# Top.net
KiCad netlist of a schematic drawn in Altium Designer
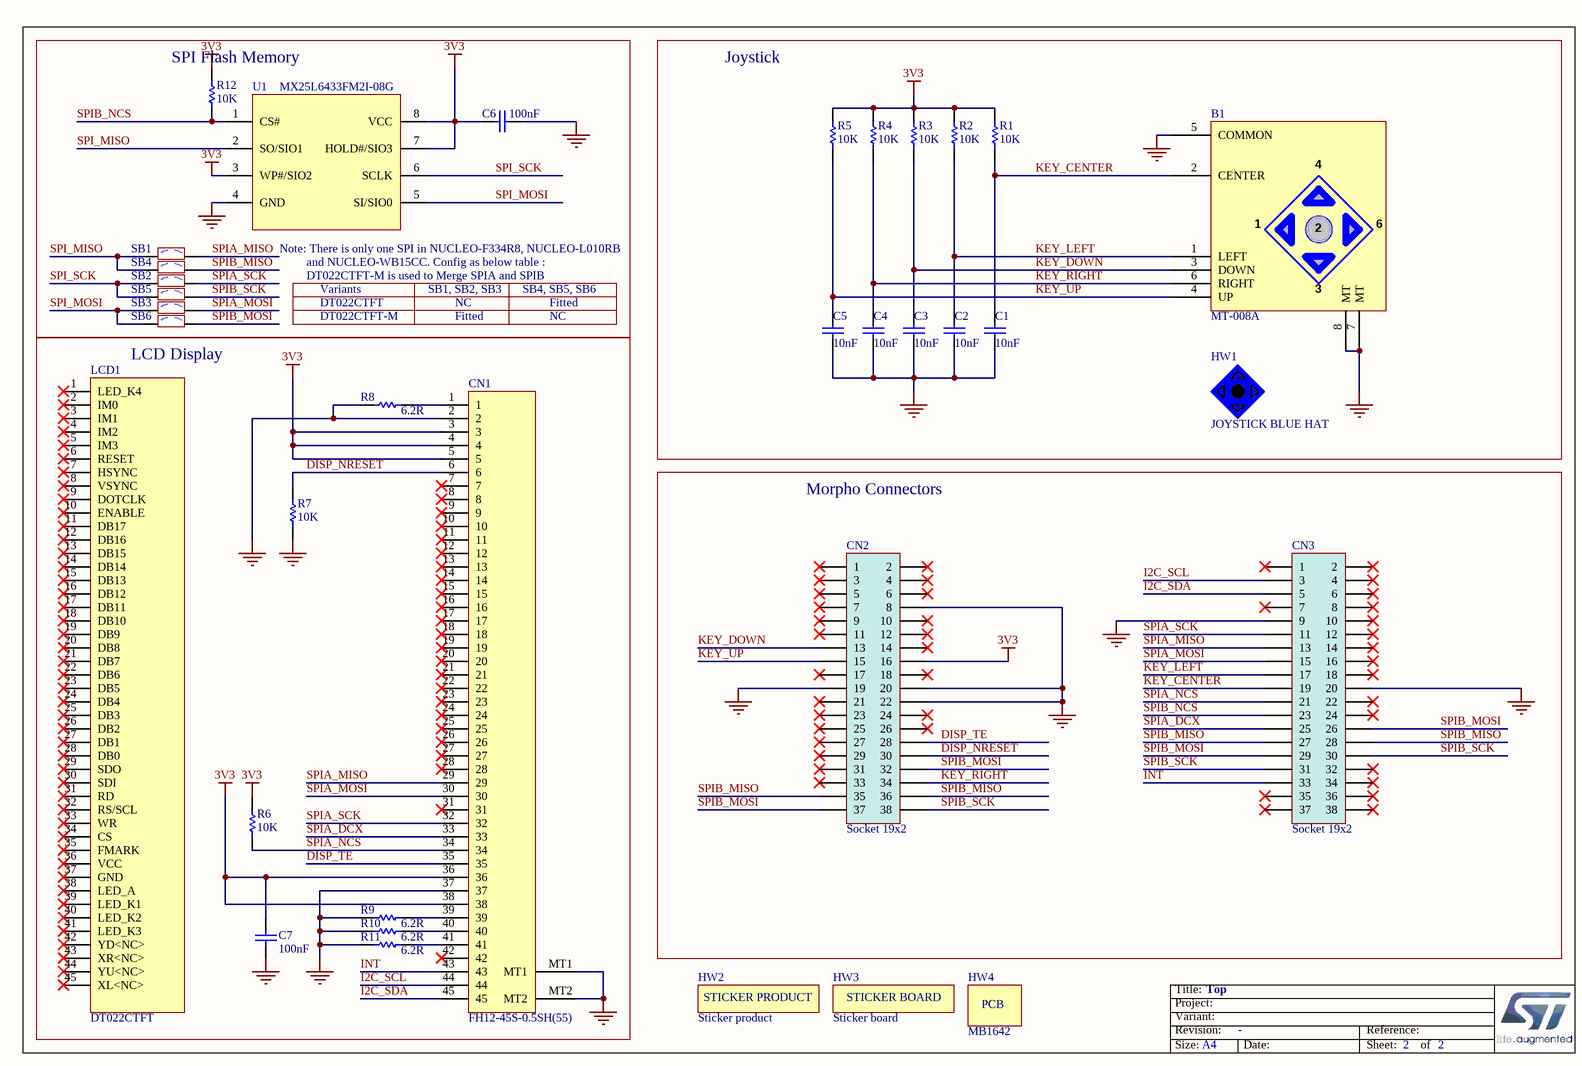
[diagram p0: Top.SchDoc]

(export (version "E")
  (design (tool "Eeschema 10.0.6"))
  (components
    (comp (ref "B1")
      (value "MT-008A")
      (footprint "SWI_XIEJIA_MT-008A_6P")
      (description "Joystick, 4 dir, 1 OK")
      (fields
        (field (name "INTERNAL_PART_NUMBER") "MCD-00132")
        (field (name "MANUFACTURER") "XIEJIA ELECTRONICS")
        (field (name "PROVIDED_BY") "SUBCO")
      )
      (libsource (lib "MCD_PARTS_database") (part "Joystick MT-008A_M"))
    )
    (comp (ref "C1")
      (value "10nF")
      (footprint "C0603")
      (description "Capacitor,10nF,100V,X7R,10%,0603")
      (fields
        (field (name "INTERNAL_PART_NUMBER") "MCD-01098")
        (field (name "MANUFACTURER_PART_NUMBER") "CC0603KRX7R0BB103")
        (field (name "PROVIDED_BY") "SUBCO")
      )
      (libsource (lib "MCD_PARTS_database") (part "Capacitor"))
    )
    (comp (ref "C2")
      (value "10nF")
      (footprint "C0603")
      (description "Capacitor,10nF,100V,X7R,10%,0603")
      (fields
        (field (name "INTERNAL_PART_NUMBER") "MCD-01098")
        (field (name "MANUFACTURER_PART_NUMBER") "CC0603KRX7R0BB103")
        (field (name "PROVIDED_BY") "SUBCO")
      )
      (libsource (lib "MCD_PARTS_database") (part "Capacitor"))
    )
    (comp (ref "C3")
      (value "10nF")
      (footprint "C0603")
      (description "Capacitor,10nF,100V,X7R,10%,0603")
      (fields
        (field (name "INTERNAL_PART_NUMBER") "MCD-01098")
        (field (name "MANUFACTURER_PART_NUMBER") "CC0603KRX7R0BB103")
        (field (name "PROVIDED_BY") "SUBCO")
      )
      (libsource (lib "MCD_PARTS_database") (part "Capacitor"))
    )
    (comp (ref "C4")
      (value "10nF")
      (footprint "C0603")
      (description "Capacitor,10nF,100V,X7R,10%,0603")
      (fields
        (field (name "INTERNAL_PART_NUMBER") "MCD-01098")
        (field (name "MANUFACTURER_PART_NUMBER") "CC0603KRX7R0BB103")
        (field (name "PROVIDED_BY") "SUBCO")
      )
      (libsource (lib "MCD_PARTS_database") (part "Capacitor"))
    )
    (comp (ref "C5")
      (value "10nF")
      (footprint "C0603")
      (description "Capacitor,10nF,100V,X7R,10%,0603")
      (fields
        (field (name "INTERNAL_PART_NUMBER") "MCD-01098")
        (field (name "MANUFACTURER_PART_NUMBER") "CC0603KRX7R0BB103")
        (field (name "PROVIDED_BY") "SUBCO")
      )
      (libsource (lib "MCD_PARTS_database") (part "Capacitor"))
    )
    (comp (ref "C6")
      (value "100nF")
      (footprint "C0603")
      (description "Capacitor, MLCC, 100nF, 16V, X7R, +/-10%, 0603, T=0,8mm")
      (fields (field (name "INTERNAL_PART_NUMBER") "MCD-00211") (field (name "MANUFACTURER") "YAGEO"))
      (libsource (lib "MCD_PARTS_database") (part "Capacitor"))
    )
    (comp (ref "C7")
      (value "100nF")
      (footprint "C0603")
      (description "Capacitor, MLCC, 100nF, 16V, X7R, +/-10%, 0603, T=0,8mm")
      (fields (field (name "INTERNAL_PART_NUMBER") "MCD-00211") (field (name "MANUFACTURER") "YAGEO"))
      (libsource (lib "MCD_PARTS_database") (part "Capacitor"))
    )
    (comp (ref "CN1")
      (value "FH12-45S-0.5SH(55)")
      (footprint "CON_HRS_FH12-45S-05SH")
      (description "45 pins P 0.5 surface mount connector")
      (fields
        (field (name "INTERNAL_PART_NUMBER") "MCD-01980")
        (field (name "MANUFACTURER") "HIROSE")
        (field (name "PROVIDED_BY") "SUBCO")
      )
      (libsource (lib "MCD_PARTS_database") (part "FH12-45S-0.5SH(55)"))
    )
    (comp (ref "CN2")
      (value "Socket 19x2")
      (footprint "CON_SAMTEC_SSW-119-01-X-D")
      (description "Socket, 19x2, 2.54mm, VR, TH, Height 8.51mm/2.64mm")
      (fields
        (field (name "INTERNAL_PART_NUMBER") "MCD-01845")
        (field (name "MANUFACTURER_PART_NUMBER") "SSW-119-01-x-D")
        (field (name "PROVIDED_BY") "SUBCO")
      )
      (libsource (lib "MCD_PARTS_database") (part "Socket 19x2"))
    )
    (comp (ref "CN3")
      (value "Socket 19x2")
      (footprint "CON_SAMTEC_SSW-119-01-X-D")
      (description "Socket, 19x2, 2.54mm, VR, TH, Height 8.51mm/2.64mm")
      (fields
        (field (name "INTERNAL_PART_NUMBER") "MCD-01845")
        (field (name "MANUFACTURER_PART_NUMBER") "SSW-119-01-x-D")
        (field (name "PROVIDED_BY") "SUBCO")
      )
      (libsource (lib "MCD_PARTS_database") (part "Socket 19x2"))
    )
    (comp (ref "HW1")
      (value "JOYSTICK BLUE HAT")
      (description "Joystick Blue Hat")
      (fields
        (field (name "INTERNAL_PART_NUMBER") "MCD-01337")
        (field (name "MANUFACTURER_PART_NUMBER") "PB-504")
        (field (name "PROVIDED_BY") "SUBCO")
      )
      (libsource (lib "MCD_PARTS_database") (part "JOYSTICK_BLUE_HAT"))
    )
    (comp (ref "HW2")
      (value "Sticker product")
      (footprint "STICKER_PRODUCT_25X5")
      (description "Sticker product 25x5 mm")
      (fields (field (name "INTERNAL_PART_NUMBER") "MCD-02189") (field (name "Comment") "STICKER_PRODUCT"))
      (libsource (lib "MCD_PARTS_database") (part "STICKER_PRODUCT"))
    )
    (comp (ref "HW3")
      (value "Sticker board")
      (footprint "STICKER_BOARD_25X5")
      (description "Sticker board 25x5 mm")
      (fields (field (name "INTERNAL_PART_NUMBER") "MCD-02190") (field (name "Comment") "STICKER_BOARD"))
      (libsource (lib "MCD_PARTS_database") (part "STICKER_BOARD"))
    )
    (comp (ref "HW4")
      (value "MB1642")
      (description "MB1642 PCB")
      (fields (field (name "INTERNAL_PART_NUMBER") "MCD-02495") (field (name "Comment") "PCB"))
      (libsource (lib "MCD_PARTS_database") (part "PCB"))
    )
    (comp (ref "LCD1")
      (value "DT022CTFT")
      (footprint "LCD_DISPLAYTECH_DT022CTFT_45P_P050")
      (description "240x320 2.2inch display")
      (fields
        (field (name "INTERNAL_PART_NUMBER") "MCD-01982")
        (field (name "MANUFACTURER") "DISPLAYTECH")
        (field (name "PROVIDED_BY") "SUBCO")
      )
      (libsource (lib "MCD_PARTS_database") (part "DT022CTFT"))
    )
    (comp (ref "R1")
      (value "10K")
      (footprint "R0603")
      (description "Resistor,10K,0603,1%,1/10W")
      (fields
        (field (name "INTERNAL_PART_NUMBER") "MCD-00220")
        (field (name "MANUFACTURER_PART_NUMBER") "RC0603FR-0710KL")
        (field (name "PROVIDED_BY") "SUBCO")
      )
      (libsource (lib "MCD_PARTS_database") (part "Resistor"))
    )
    (comp (ref "R2")
      (value "10K")
      (footprint "R0603")
      (description "Resistor,10K,0603,1%,1/10W")
      (fields
        (field (name "INTERNAL_PART_NUMBER") "MCD-00220")
        (field (name "MANUFACTURER_PART_NUMBER") "RC0603FR-0710KL")
        (field (name "PROVIDED_BY") "SUBCO")
      )
      (libsource (lib "MCD_PARTS_database") (part "Resistor"))
    )
    (comp (ref "R3")
      (value "10K")
      (footprint "R0603")
      (description "Resistor,10K,0603,1%,1/10W")
      (fields
        (field (name "INTERNAL_PART_NUMBER") "MCD-00220")
        (field (name "MANUFACTURER_PART_NUMBER") "RC0603FR-0710KL")
        (field (name "PROVIDED_BY") "SUBCO")
      )
      (libsource (lib "MCD_PARTS_database") (part "Resistor"))
    )
    (comp (ref "R4")
      (value "10K")
      (footprint "R0603")
      (description "Resistor,10K,0603,1%,1/10W")
      (fields
        (field (name "INTERNAL_PART_NUMBER") "MCD-00220")
        (field (name "MANUFACTURER_PART_NUMBER") "RC0603FR-0710KL")
        (field (name "PROVIDED_BY") "SUBCO")
      )
      (libsource (lib "MCD_PARTS_database") (part "Resistor"))
    )
    (comp (ref "R5")
      (value "10K")
      (footprint "R0603")
      (description "Resistor,10K,0603,1%,1/10W")
      (fields
        (field (name "INTERNAL_PART_NUMBER") "MCD-00220")
        (field (name "MANUFACTURER_PART_NUMBER") "RC0603FR-0710KL")
        (field (name "PROVIDED_BY") "SUBCO")
      )
      (libsource (lib "MCD_PARTS_database") (part "Resistor"))
    )
    (comp (ref "R6")
      (value "10K")
      (footprint "R0603")
      (description "Resistor,10K,0603,1%,1/10W")
      (fields
        (field (name "INTERNAL_PART_NUMBER") "MCD-00220")
        (field (name "MANUFACTURER_PART_NUMBER") "RC0603FR-0710KL")
        (field (name "PROVIDED_BY") "SUBCO")
      )
      (libsource (lib "MCD_PARTS_database") (part "Resistor"))
    )
    (comp (ref "R7")
      (value "10K")
      (footprint "R0603")
      (description "Resistor,10K,0603,1%,1/10W")
      (fields
        (field (name "INTERNAL_PART_NUMBER") "MCD-00220")
        (field (name "MANUFACTURER_PART_NUMBER") "RC0603FR-0710KL")
        (field (name "PROVIDED_BY") "SUBCO")
      )
      (libsource (lib "MCD_PARTS_database") (part "Resistor"))
    )
    (comp (ref "R8")
      (value "6.2R")
      (footprint "R1206_H0P55")
      (description "Resistor,6.2R,1206,1%,0.5W")
      (fields
        (field (name "INTERNAL_PART_NUMBER") "MCD-02101")
        (field (name "MANUFACTURER_PART_NUMBER") "ERJ8BQF6R2V")
        (field (name "PROVIDED_BY") "SUBCO")
      )
      (libsource (lib "MCD_PARTS_database") (part "Resistor"))
    )
    (comp (ref "R9")
      (value "6.2R")
      (footprint "R1206_H0P55")
      (description "Resistor,6.2R,1206,1%,0.5W")
      (fields
        (field (name "INTERNAL_PART_NUMBER") "MCD-02101")
        (field (name "MANUFACTURER_PART_NUMBER") "ERJ8BQF6R2V")
        (field (name "PROVIDED_BY") "SUBCO")
      )
      (libsource (lib "MCD_PARTS_database") (part "Resistor"))
    )
    (comp (ref "R10")
      (value "6.2R")
      (footprint "R1206_H0P55")
      (description "Resistor,6.2R,1206,1%,0.5W")
      (fields
        (field (name "INTERNAL_PART_NUMBER") "MCD-02101")
        (field (name "MANUFACTURER_PART_NUMBER") "ERJ8BQF6R2V")
        (field (name "PROVIDED_BY") "SUBCO")
      )
      (libsource (lib "MCD_PARTS_database") (part "Resistor"))
    )
    (comp (ref "R11")
      (value "6.2R")
      (footprint "R1206_H0P55")
      (description "Resistor,6.2R,1206,1%,0.5W")
      (fields
        (field (name "INTERNAL_PART_NUMBER") "MCD-02101")
        (field (name "MANUFACTURER_PART_NUMBER") "ERJ8BQF6R2V")
        (field (name "PROVIDED_BY") "SUBCO")
      )
      (libsource (lib "MCD_PARTS_database") (part "Resistor"))
    )
    (comp (ref "R12")
      (value "10K")
      (footprint "R0603")
      (description "Resistor,10K,0603,1%,1/10W")
      (fields
        (field (name "INTERNAL_PART_NUMBER") "MCD-00220")
        (field (name "MANUFACTURER_PART_NUMBER") "RC0603FR-0710KL")
        (field (name "PROVIDED_BY") "SUBCO")
      )
      (libsource (lib "MCD_PARTS_database") (part "Resistor"))
    )
    (comp (ref "SB1")
      (value "SB_OFF")
      (footprint "SOLDER-BRIDGE_R0603-0R")
      (description "Solder Bridge OFF")
      (fields (field (name "INTERNAL_PART_NUMBER") "MCD-00072") (field (name "MANUFACTURER") "YAGEO"))
      (libsource (lib "MCD_PARTS_database") (part "SB_OFF"))
    )
    (comp (ref "SB2")
      (value "SB_OFF")
      (footprint "SOLDER-BRIDGE_R0603-0R")
      (description "Solder Bridge OFF")
      (fields (field (name "INTERNAL_PART_NUMBER") "MCD-00072") (field (name "MANUFACTURER") "YAGEO"))
      (libsource (lib "MCD_PARTS_database") (part "SB_OFF"))
    )
    (comp (ref "SB3")
      (value "SB_OFF")
      (footprint "SOLDER-BRIDGE_R0603-0R")
      (description "Solder Bridge OFF")
      (fields (field (name "INTERNAL_PART_NUMBER") "MCD-00072") (field (name "MANUFACTURER") "YAGEO"))
      (libsource (lib "MCD_PARTS_database") (part "SB_OFF"))
    )
    (comp (ref "SB4")
      (value "SB_OFF")
      (footprint "SOLDER-BRIDGE_R0603-0R")
      (description "Solder Bridge OFF")
      (fields (field (name "INTERNAL_PART_NUMBER") "MCD-00072") (field (name "MANUFACTURER") "YAGEO"))
      (libsource (lib "MCD_PARTS_database") (part "SB_OFF"))
    )
    (comp (ref "SB5")
      (value "SB_OFF")
      (footprint "SOLDER-BRIDGE_R0603-0R")
      (description "Solder Bridge OFF")
      (fields (field (name "INTERNAL_PART_NUMBER") "MCD-00072") (field (name "MANUFACTURER") "YAGEO"))
      (libsource (lib "MCD_PARTS_database") (part "SB_OFF"))
    )
    (comp (ref "SB6")
      (value "SB_OFF")
      (footprint "SOLDER-BRIDGE_R0603-0R")
      (description "Solder Bridge OFF")
      (fields (field (name "INTERNAL_PART_NUMBER") "MCD-00072") (field (name "MANUFACTURER") "YAGEO"))
      (libsource (lib "MCD_PARTS_database") (part "SB_OFF"))
    )
    (comp (ref "U1")
      (value "MX25L6433FM2I-08G")
      (footprint "ICC_SOP8_5P23X5P28_P127")
      (fields
        (field (name "INTERNAL_PART_NUMBER") "MCD-01981")
        (field (name "MANUFACTURER") "MACRONIX")
        (field (name "PROVIDED_BY") "SUBCO")
      )
      (libsource (lib "MCD_PARTS_database") (part "MX25L6433FM2I-08G"))
    )
  )
  (nets
    (net (code "1") (name "/DISP_NRESET") (class "Default")
      (node (ref "CN1") (pin "6") (pinfunction "6_6") (pintype "passive"))
      (node (ref "CN2") (pin "30") (pinfunction "30_30") (pintype "passive"))
      (node (ref "R7") (pin "2") (pinfunction "2_2") (pintype "passive"))
    )
    (net (code "2") (name "/DISP_TE") (class "Default")
      (node (ref "CN1") (pin "35") (pinfunction "35_35") (pintype "passive"))
      (node (ref "CN2") (pin "28") (pinfunction "28_28") (pintype "passive"))
    )
    (net (code "3") (name "/I2C_SCL") (class "Default")
      (node (ref "CN1") (pin "44") (pinfunction "44_44") (pintype "passive"))
      (node (ref "CN3") (pin "3") (pinfunction "3_3") (pintype "passive"))
    )
    (net (code "4") (name "/I2C_SDA") (class "Default")
      (node (ref "CN1") (pin "45") (pinfunction "45_45") (pintype "passive"))
      (node (ref "CN3") (pin "5") (pinfunction "5_5") (pintype "passive"))
    )
    (net (code "5") (name "/INT") (class "Default")
      (node (ref "CN1") (pin "43") (pinfunction "43_43") (pintype "passive"))
      (node (ref "CN3") (pin "33") (pinfunction "33_33") (pintype "passive"))
    )
    (net (code "6") (name "/KEY_CENTER") (class "Default")
      (node (ref "B1") (pin "2") (pinfunction "CENTER_2") (pintype "passive"))
      (node (ref "C1") (pin "2") (pinfunction "2_2") (pintype "passive"))
      (node (ref "CN3") (pin "19") (pinfunction "19_19") (pintype "passive"))
      (node (ref "R1") (pin "2") (pinfunction "2_2") (pintype "passive"))
    )
    (net (code "7") (name "/KEY_DOWN") (class "Default")
      (node (ref "B1") (pin "3") (pinfunction "DOWN_3") (pintype "passive"))
      (node (ref "C3") (pin "2") (pinfunction "2_2") (pintype "passive"))
      (node (ref "CN2") (pin "13") (pinfunction "13_13") (pintype "passive"))
      (node (ref "R3") (pin "1") (pinfunction "1_1") (pintype "passive"))
    )
    (net (code "8") (name "/KEY_LEFT") (class "Default")
      (node (ref "B1") (pin "1") (pinfunction "LEFT_1") (pintype "passive"))
      (node (ref "C2") (pin "2") (pinfunction "2_2") (pintype "passive"))
      (node (ref "CN3") (pin "17") (pinfunction "17_17") (pintype "passive"))
      (node (ref "R2") (pin "1") (pinfunction "1_1") (pintype "passive"))
    )
    (net (code "9") (name "/KEY_RIGHT") (class "Default")
      (node (ref "B1") (pin "6") (pinfunction "RIGHT_6") (pintype "passive"))
      (node (ref "C4") (pin "2") (pinfunction "2_2") (pintype "passive"))
      (node (ref "CN2") (pin "34") (pinfunction "34_34") (pintype "passive"))
      (node (ref "R4") (pin "1") (pinfunction "1_1") (pintype "passive"))
    )
    (net (code "10") (name "/KEY_UP") (class "Default")
      (node (ref "B1") (pin "4") (pinfunction "UP_4") (pintype "passive"))
      (node (ref "C5") (pin "2") (pinfunction "2_2") (pintype "passive"))
      (node (ref "CN2") (pin "15") (pinfunction "15_15") (pintype "passive"))
      (node (ref "R5") (pin "1") (pinfunction "1_1") (pintype "passive"))
    )
    (net (code "11") (name "/SPIA_DCX") (class "Default")
      (node (ref "CN1") (pin "33") (pinfunction "33_33") (pintype "passive"))
      (node (ref "CN3") (pin "25") (pinfunction "25_25") (pintype "passive"))
    )
    (net (code "12") (name "/SPIA_MISO") (class "Default")
      (node (ref "CN1") (pin "29") (pinfunction "29_29") (pintype "passive"))
      (node (ref "CN3") (pin "13") (pinfunction "13_13") (pintype "passive"))
      (node (ref "SB1") (pin "2") (pinfunction "2_2") (pintype "passive"))
    )
    (net (code "13") (name "/SPIA_MOSI") (class "Default")
      (node (ref "CN1") (pin "30") (pinfunction "30_30") (pintype "passive"))
      (node (ref "CN3") (pin "15") (pinfunction "15_15") (pintype "passive"))
      (node (ref "SB3") (pin "2") (pinfunction "2_2") (pintype "passive"))
    )
    (net (code "14") (name "/SPIA_NCS") (class "Default")
      (node (ref "CN1") (pin "34") (pinfunction "34_34") (pintype "passive"))
      (node (ref "CN3") (pin "21") (pinfunction "21_21") (pintype "passive"))
      (node (ref "R6") (pin "1") (pinfunction "1_1") (pintype "passive"))
    )
    (net (code "15") (name "/SPIA_SCK") (class "Default")
      (node (ref "CN1") (pin "32") (pinfunction "32_32") (pintype "passive"))
      (node (ref "CN3") (pin "11") (pinfunction "11_11") (pintype "passive"))
      (node (ref "SB2") (pin "2") (pinfunction "2_2") (pintype "passive"))
    )
    (net (code "16") (name "/SPIB_MISO") (class "Default")
      (node (ref "CN2") (pin "35") (pinfunction "35_35") (pintype "passive"))
      (node (ref "CN2") (pin "36") (pinfunction "36_36") (pintype "passive"))
      (node (ref "CN3") (pin "27") (pinfunction "27_27") (pintype "passive"))
      (node (ref "CN3") (pin "28") (pinfunction "28_28") (pintype "passive"))
      (node (ref "SB4") (pin "2") (pinfunction "2_2") (pintype "passive"))
    )
    (net (code "17") (name "/SPIB_MOSI") (class "Default")
      (node (ref "CN2") (pin "32") (pinfunction "32_32") (pintype "passive"))
      (node (ref "CN2") (pin "37") (pinfunction "37_37") (pintype "passive"))
      (node (ref "CN3") (pin "26") (pinfunction "26_26") (pintype "passive"))
      (node (ref "CN3") (pin "29") (pinfunction "29_29") (pintype "passive"))
      (node (ref "SB6") (pin "2") (pinfunction "2_2") (pintype "passive"))
    )
    (net (code "18") (name "/SPIB_NCS") (class "Default")
      (node (ref "CN3") (pin "23") (pinfunction "23_23") (pintype "passive"))
      (node (ref "R12") (pin "2") (pinfunction "2_2") (pintype "passive"))
      (node (ref "U1") (pin "1") (pinfunction "CS#_1") (pintype "passive"))
    )
    (net (code "19") (name "/SPIB_SCK") (class "Default")
      (node (ref "CN2") (pin "38") (pinfunction "38_38") (pintype "passive"))
      (node (ref "CN3") (pin "30") (pinfunction "30_30") (pintype "passive"))
      (node (ref "CN3") (pin "31") (pinfunction "31_31") (pintype "passive"))
      (node (ref "SB5") (pin "2") (pinfunction "2_2") (pintype "passive"))
    )
    (net (code "20") (name "/SPI_MISO") (class "Default")
      (node (ref "SB1") (pin "1") (pinfunction "1_1") (pintype "passive"))
      (node (ref "SB4") (pin "1") (pinfunction "1_1") (pintype "passive"))
      (node (ref "U1") (pin "2") (pinfunction "SO/SIO1_2") (pintype "passive"))
    )
    (net (code "21") (name "/SPI_MOSI") (class "Default")
      (node (ref "SB3") (pin "1") (pinfunction "1_1") (pintype "passive"))
      (node (ref "SB6") (pin "1") (pinfunction "1_1") (pintype "passive"))
      (node (ref "U1") (pin "5") (pinfunction "SI/SIO0_5") (pintype "passive"))
    )
    (net (code "22") (name "/SPI_SCK") (class "Default")
      (node (ref "SB2") (pin "1") (pinfunction "1_1") (pintype "passive"))
      (node (ref "SB5") (pin "1") (pinfunction "1_1") (pintype "passive"))
      (node (ref "U1") (pin "6") (pinfunction "SCLK_6") (pintype "passive"))
    )
    (net (code "23") (name "3V3") (class "Default")
      (node (ref "C6") (pin "1") (pinfunction "1_1") (pintype "passive"))
      (node (ref "C7") (pin "2") (pinfunction "2_2") (pintype "passive"))
      (node (ref "CN1") (pin "3") (pinfunction "3_3") (pintype "passive"))
      (node (ref "CN1") (pin "36") (pinfunction "36_36") (pintype "passive"))
      (node (ref "CN1") (pin "38") (pinfunction "38_38") (pintype "passive"))
      (node (ref "CN1") (pin "4") (pinfunction "4_4") (pintype "passive"))
      (node (ref "CN1") (pin "5") (pinfunction "5_5") (pintype "passive"))
      (node (ref "CN2") (pin "16") (pinfunction "16_16") (pintype "passive"))
      (node (ref "R1") (pin "1") (pinfunction "1_1") (pintype "passive"))
      (node (ref "R12") (pin "1") (pinfunction "1_1") (pintype "passive"))
      (node (ref "R2") (pin "2") (pinfunction "2_2") (pintype "passive"))
      (node (ref "R3") (pin "2") (pinfunction "2_2") (pintype "passive"))
      (node (ref "R4") (pin "2") (pinfunction "2_2") (pintype "passive"))
      (node (ref "R5") (pin "2") (pinfunction "2_2") (pintype "passive"))
      (node (ref "R6") (pin "2") (pinfunction "2_2") (pintype "passive"))
      (node (ref "U1") (pin "3") (pinfunction "WP#/SIO2_3") (pintype "passive"))
      (node (ref "U1") (pin "7") (pinfunction "HOLD#/SIO3_7") (pintype "passive"))
      (node (ref "U1") (pin "8") (pinfunction "VCC_8") (pintype "passive"))
    )
    (net (code "24") (name "GND") (class "Default")
      (node (ref "B1") (pin "5") (pinfunction "COMMON_5") (pintype "passive"))
      (node (ref "B1") (pin "7") (pinfunction "MT_7") (pintype "passive"))
      (node (ref "B1") (pin "8") (pinfunction "MT_8") (pintype "passive"))
      (node (ref "C1") (pin "1") (pinfunction "1_1") (pintype "passive"))
      (node (ref "C2") (pin "1") (pinfunction "1_1") (pintype "passive"))
      (node (ref "C3") (pin "1") (pinfunction "1_1") (pintype "passive"))
      (node (ref "C4") (pin "1") (pinfunction "1_1") (pintype "passive"))
      (node (ref "C5") (pin "1") (pinfunction "1_1") (pintype "passive"))
      (node (ref "C6") (pin "2") (pinfunction "2_2") (pintype "passive"))
      (node (ref "C7") (pin "1") (pinfunction "1_1") (pintype "passive"))
      (node (ref "CN1") (pin "2") (pinfunction "2_2") (pintype "passive"))
      (node (ref "CN1") (pin "37") (pinfunction "37_37") (pintype "passive"))
      (node (ref "CN1") (pin "MT1") (pinfunction "MT1_MT1") (pintype "passive"))
      (node (ref "CN1") (pin "MT2") (pinfunction "MT2_MT2") (pintype "passive"))
      (node (ref "CN2") (pin "19") (pinfunction "19_19") (pintype "passive"))
      (node (ref "CN2") (pin "20") (pinfunction "20_20") (pintype "passive"))
      (node (ref "CN2") (pin "22") (pinfunction "22_22") (pintype "passive"))
      (node (ref "CN2") (pin "8") (pinfunction "8_8") (pintype "passive"))
      (node (ref "CN3") (pin "20") (pinfunction "20_20") (pintype "passive"))
      (node (ref "CN3") (pin "9") (pinfunction "9_9") (pintype "passive"))
      (node (ref "R10") (pin "1") (pinfunction "1_1") (pintype "passive"))
      (node (ref "R11") (pin "1") (pinfunction "1_1") (pintype "passive"))
      (node (ref "R7") (pin "1") (pinfunction "1_1") (pintype "passive"))
      (node (ref "R8") (pin "1") (pinfunction "1_1") (pintype "passive"))
      (node (ref "R9") (pin "1") (pinfunction "1_1") (pintype "passive"))
      (node (ref "U1") (pin "4") (pinfunction "GND_4") (pintype "passive"))
    )
    (net (code "25") (name "Net-(CN1-Pad1)") (class "Default")
      (node (ref "CN1") (pin "1") (pinfunction "1_1") (pintype "passive"))
      (node (ref "R8") (pin "2") (pinfunction "2_2") (pintype "passive"))
    )
    (net (code "26") (name "Net-(CN1-Pad39)") (class "Default")
      (node (ref "CN1") (pin "39") (pinfunction "39_39") (pintype "passive"))
      (node (ref "R9") (pin "2") (pinfunction "2_2") (pintype "passive"))
    )
    (net (code "27") (name "Net-(CN1-Pad40)") (class "Default")
      (node (ref "CN1") (pin "40") (pinfunction "40_40") (pintype "passive"))
      (node (ref "R10") (pin "2") (pinfunction "2_2") (pintype "passive"))
    )
    (net (code "28") (name "Net-(CN1-Pad41)") (class "Default")
      (node (ref "CN1") (pin "41") (pinfunction "41_41") (pintype "passive"))
      (node (ref "R11") (pin "2") (pinfunction "2_2") (pintype "passive"))
    )
    (net (code "29") (name "unconnected-(CN1-Pad7)") (class "Default")
      (node (ref "CN1") (pin "7") (pinfunction "7_7") (pintype "passive+no_connect"))
    )
    (net (code "30") (name "unconnected-(CN1-Pad8)") (class "Default")
      (node (ref "CN1") (pin "8") (pinfunction "8_8") (pintype "passive+no_connect"))
    )
    (net (code "31") (name "unconnected-(CN1-Pad9)") (class "Default")
      (node (ref "CN1") (pin "9") (pinfunction "9_9") (pintype "passive+no_connect"))
    )
    (net (code "32") (name "unconnected-(CN1-Pad10)") (class "Default")
      (node (ref "CN1") (pin "10") (pinfunction "10_10") (pintype "passive+no_connect"))
    )
    (net (code "33") (name "unconnected-(CN1-Pad11)") (class "Default")
      (node (ref "CN1") (pin "11") (pinfunction "11_11") (pintype "passive+no_connect"))
    )
    (net (code "34") (name "unconnected-(CN1-Pad12)") (class "Default")
      (node (ref "CN1") (pin "12") (pinfunction "12_12") (pintype "passive+no_connect"))
    )
    (net (code "35") (name "unconnected-(CN1-Pad13)") (class "Default")
      (node (ref "CN1") (pin "13") (pinfunction "13_13") (pintype "passive+no_connect"))
    )
    (net (code "36") (name "unconnected-(CN1-Pad14)") (class "Default")
      (node (ref "CN1") (pin "14") (pinfunction "14_14") (pintype "passive+no_connect"))
    )
    (net (code "37") (name "unconnected-(CN1-Pad15)") (class "Default")
      (node (ref "CN1") (pin "15") (pinfunction "15_15") (pintype "passive+no_connect"))
    )
    (net (code "38") (name "unconnected-(CN1-Pad16)") (class "Default")
      (node (ref "CN1") (pin "16") (pinfunction "16_16") (pintype "passive+no_connect"))
    )
    (net (code "39") (name "unconnected-(CN1-Pad17)") (class "Default")
      (node (ref "CN1") (pin "17") (pinfunction "17_17") (pintype "passive+no_connect"))
    )
    (net (code "40") (name "unconnected-(CN1-Pad18)") (class "Default")
      (node (ref "CN1") (pin "18") (pinfunction "18_18") (pintype "passive+no_connect"))
    )
    (net (code "41") (name "unconnected-(CN1-Pad19)") (class "Default")
      (node (ref "CN1") (pin "19") (pinfunction "19_19") (pintype "passive+no_connect"))
    )
    (net (code "42") (name "unconnected-(CN1-Pad20)") (class "Default")
      (node (ref "CN1") (pin "20") (pinfunction "20_20") (pintype "passive+no_connect"))
    )
    (net (code "43") (name "unconnected-(CN1-Pad21)") (class "Default")
      (node (ref "CN1") (pin "21") (pinfunction "21_21") (pintype "passive+no_connect"))
    )
    (net (code "44") (name "unconnected-(CN1-Pad22)") (class "Default")
      (node (ref "CN1") (pin "22") (pinfunction "22_22") (pintype "passive+no_connect"))
    )
    (net (code "45") (name "unconnected-(CN1-Pad23)") (class "Default")
      (node (ref "CN1") (pin "23") (pinfunction "23_23") (pintype "passive+no_connect"))
    )
    (net (code "46") (name "unconnected-(CN1-Pad24)") (class "Default")
      (node (ref "CN1") (pin "24") (pinfunction "24_24") (pintype "passive+no_connect"))
    )
    (net (code "47") (name "unconnected-(CN1-Pad25)") (class "Default")
      (node (ref "CN1") (pin "25") (pinfunction "25_25") (pintype "passive+no_connect"))
    )
    (net (code "48") (name "unconnected-(CN1-Pad26)") (class "Default")
      (node (ref "CN1") (pin "26") (pinfunction "26_26") (pintype "passive+no_connect"))
    )
    (net (code "49") (name "unconnected-(CN1-Pad27)") (class "Default")
      (node (ref "CN1") (pin "27") (pinfunction "27_27") (pintype "passive+no_connect"))
    )
    (net (code "50") (name "unconnected-(CN1-Pad28)") (class "Default")
      (node (ref "CN1") (pin "28") (pinfunction "28_28") (pintype "passive+no_connect"))
    )
    (net (code "51") (name "unconnected-(CN1-Pad31)") (class "Default")
      (node (ref "CN1") (pin "31") (pinfunction "31_31") (pintype "passive+no_connect"))
    )
    (net (code "52") (name "unconnected-(CN1-Pad42)") (class "Default")
      (node (ref "CN1") (pin "42") (pinfunction "42_42") (pintype "passive+no_connect"))
    )
    (net (code "53") (name "unconnected-(CN2-Pad1)") (class "Default")
      (node (ref "CN2") (pin "1") (pinfunction "1_1") (pintype "passive+no_connect"))
    )
    (net (code "54") (name "unconnected-(CN2-Pad2)") (class "Default")
      (node (ref "CN2") (pin "2") (pinfunction "2_2") (pintype "passive+no_connect"))
    )
    (net (code "55") (name "unconnected-(CN2-Pad3)") (class "Default")
      (node (ref "CN2") (pin "3") (pinfunction "3_3") (pintype "passive+no_connect"))
    )
    (net (code "56") (name "unconnected-(CN2-Pad4)") (class "Default")
      (node (ref "CN2") (pin "4") (pinfunction "4_4") (pintype "passive+no_connect"))
    )
    (net (code "57") (name "unconnected-(CN2-Pad5)") (class "Default")
      (node (ref "CN2") (pin "5") (pinfunction "5_5") (pintype "passive+no_connect"))
    )
    (net (code "58") (name "unconnected-(CN2-Pad6)") (class "Default")
      (node (ref "CN2") (pin "6") (pinfunction "6_6") (pintype "passive+no_connect"))
    )
    (net (code "59") (name "unconnected-(CN2-Pad7)") (class "Default")
      (node (ref "CN2") (pin "7") (pinfunction "7_7") (pintype "passive+no_connect"))
    )
    (net (code "60") (name "unconnected-(CN2-Pad9)") (class "Default")
      (node (ref "CN2") (pin "9") (pinfunction "9_9") (pintype "passive+no_connect"))
    )
    (net (code "61") (name "unconnected-(CN2-Pad10)") (class "Default")
      (node (ref "CN2") (pin "10") (pinfunction "10_10") (pintype "passive+no_connect"))
    )
    (net (code "62") (name "unconnected-(CN2-Pad11)") (class "Default")
      (node (ref "CN2") (pin "11") (pinfunction "11_11") (pintype "passive+no_connect"))
    )
    (net (code "63") (name "unconnected-(CN2-Pad12)") (class "Default")
      (node (ref "CN2") (pin "12") (pinfunction "12_12") (pintype "passive+no_connect"))
    )
    (net (code "64") (name "unconnected-(CN2-Pad14)") (class "Default")
      (node (ref "CN2") (pin "14") (pinfunction "14_14") (pintype "passive+no_connect"))
    )
    (net (code "65") (name "unconnected-(CN2-Pad17)") (class "Default")
      (node (ref "CN2") (pin "17") (pinfunction "17_17") (pintype "passive+no_connect"))
    )
    (net (code "66") (name "unconnected-(CN2-Pad18)") (class "Default")
      (node (ref "CN2") (pin "18") (pinfunction "18_18") (pintype "passive+no_connect"))
    )
    (net (code "67") (name "unconnected-(CN2-Pad21)") (class "Default")
      (node (ref "CN2") (pin "21") (pinfunction "21_21") (pintype "passive+no_connect"))
    )
    (net (code "68") (name "unconnected-(CN2-Pad23)") (class "Default")
      (node (ref "CN2") (pin "23") (pinfunction "23_23") (pintype "passive+no_connect"))
    )
    (net (code "69") (name "unconnected-(CN2-Pad24)") (class "Default")
      (node (ref "CN2") (pin "24") (pinfunction "24_24") (pintype "passive+no_connect"))
    )
    (net (code "70") (name "unconnected-(CN2-Pad25)") (class "Default")
      (node (ref "CN2") (pin "25") (pinfunction "25_25") (pintype "passive+no_connect"))
    )
    (net (code "71") (name "unconnected-(CN2-Pad26)") (class "Default")
      (node (ref "CN2") (pin "26") (pinfunction "26_26") (pintype "passive+no_connect"))
    )
    (net (code "72") (name "unconnected-(CN2-Pad27)") (class "Default")
      (node (ref "CN2") (pin "27") (pinfunction "27_27") (pintype "passive+no_connect"))
    )
    (net (code "73") (name "unconnected-(CN2-Pad29)") (class "Default")
      (node (ref "CN2") (pin "29") (pinfunction "29_29") (pintype "passive+no_connect"))
    )
    (net (code "74") (name "unconnected-(CN2-Pad31)") (class "Default")
      (node (ref "CN2") (pin "31") (pinfunction "31_31") (pintype "passive+no_connect"))
    )
    (net (code "75") (name "unconnected-(CN2-Pad33)") (class "Default")
      (node (ref "CN2") (pin "33") (pinfunction "33_33") (pintype "passive+no_connect"))
    )
    (net (code "76") (name "unconnected-(CN3-Pad1)") (class "Default")
      (node (ref "CN3") (pin "1") (pinfunction "1_1") (pintype "passive+no_connect"))
    )
    (net (code "77") (name "unconnected-(CN3-Pad2)") (class "Default")
      (node (ref "CN3") (pin "2") (pinfunction "2_2") (pintype "passive+no_connect"))
    )
    (net (code "78") (name "unconnected-(CN3-Pad4)") (class "Default")
      (node (ref "CN3") (pin "4") (pinfunction "4_4") (pintype "passive+no_connect"))
    )
    (net (code "79") (name "unconnected-(CN3-Pad6)") (class "Default")
      (node (ref "CN3") (pin "6") (pinfunction "6_6") (pintype "passive+no_connect"))
    )
    (net (code "80") (name "unconnected-(CN3-Pad7)") (class "Default")
      (node (ref "CN3") (pin "7") (pinfunction "7_7") (pintype "passive+no_connect"))
    )
    (net (code "81") (name "unconnected-(CN3-Pad8)") (class "Default")
      (node (ref "CN3") (pin "8") (pinfunction "8_8") (pintype "passive+no_connect"))
    )
    (net (code "82") (name "unconnected-(CN3-Pad10)") (class "Default")
      (node (ref "CN3") (pin "10") (pinfunction "10_10") (pintype "passive+no_connect"))
    )
    (net (code "83") (name "unconnected-(CN3-Pad12)") (class "Default")
      (node (ref "CN3") (pin "12") (pinfunction "12_12") (pintype "passive+no_connect"))
    )
    (net (code "84") (name "unconnected-(CN3-Pad14)") (class "Default")
      (node (ref "CN3") (pin "14") (pinfunction "14_14") (pintype "passive+no_connect"))
    )
    (net (code "85") (name "unconnected-(CN3-Pad16)") (class "Default")
      (node (ref "CN3") (pin "16") (pinfunction "16_16") (pintype "passive+no_connect"))
    )
    (net (code "86") (name "unconnected-(CN3-Pad18)") (class "Default")
      (node (ref "CN3") (pin "18") (pinfunction "18_18") (pintype "passive+no_connect"))
    )
    (net (code "87") (name "unconnected-(CN3-Pad22)") (class "Default")
      (node (ref "CN3") (pin "22") (pinfunction "22_22") (pintype "passive+no_connect"))
    )
    (net (code "88") (name "unconnected-(CN3-Pad24)") (class "Default")
      (node (ref "CN3") (pin "24") (pinfunction "24_24") (pintype "passive+no_connect"))
    )
    (net (code "89") (name "unconnected-(CN3-Pad32)") (class "Default")
      (node (ref "CN3") (pin "32") (pinfunction "32_32") (pintype "passive+no_connect"))
    )
    (net (code "90") (name "unconnected-(CN3-Pad34)") (class "Default")
      (node (ref "CN3") (pin "34") (pinfunction "34_34") (pintype "passive+no_connect"))
    )
    (net (code "91") (name "unconnected-(CN3-Pad35)") (class "Default")
      (node (ref "CN3") (pin "35") (pinfunction "35_35") (pintype "passive+no_connect"))
    )
    (net (code "92") (name "unconnected-(CN3-Pad36)") (class "Default")
      (node (ref "CN3") (pin "36") (pinfunction "36_36") (pintype "passive+no_connect"))
    )
    (net (code "93") (name "unconnected-(CN3-Pad37)") (class "Default")
      (node (ref "CN3") (pin "37") (pinfunction "37_37") (pintype "passive+no_connect"))
    )
    (net (code "94") (name "unconnected-(CN3-Pad38)") (class "Default")
      (node (ref "CN3") (pin "38") (pinfunction "38_38") (pintype "passive+no_connect"))
    )
    (net (code "95") (name "unconnected-(LCD1-CS-Pad34)") (class "Default")
      (node (ref "LCD1") (pin "34") (pinfunction "CS_34") (pintype "passive+no_connect"))
    )
    (net (code "96") (name "unconnected-(LCD1-DB0-Pad28)") (class "Default")
      (node (ref "LCD1") (pin "28") (pinfunction "DB0_28") (pintype "passive+no_connect"))
    )
    (net (code "97") (name "unconnected-(LCD1-DB1-Pad27)") (class "Default")
      (node (ref "LCD1") (pin "27") (pinfunction "DB1_27") (pintype "passive+no_connect"))
    )
    (net (code "98") (name "unconnected-(LCD1-DB2-Pad26)") (class "Default")
      (node (ref "LCD1") (pin "26") (pinfunction "DB2_26") (pintype "passive+no_connect"))
    )
    (net (code "99") (name "unconnected-(LCD1-DB3-Pad25)") (class "Default")
      (node (ref "LCD1") (pin "25") (pinfunction "DB3_25") (pintype "passive+no_connect"))
    )
    (net (code "100") (name "unconnected-(LCD1-DB4-Pad24)") (class "Default")
      (node (ref "LCD1") (pin "24") (pinfunction "DB4_24") (pintype "passive+no_connect"))
    )
    (net (code "101") (name "unconnected-(LCD1-DB5-Pad23)") (class "Default")
      (node (ref "LCD1") (pin "23") (pinfunction "DB5_23") (pintype "passive+no_connect"))
    )
    (net (code "102") (name "unconnected-(LCD1-DB6-Pad22)") (class "Default")
      (node (ref "LCD1") (pin "22") (pinfunction "DB6_22") (pintype "passive+no_connect"))
    )
    (net (code "103") (name "unconnected-(LCD1-DB7-Pad21)") (class "Default")
      (node (ref "LCD1") (pin "21") (pinfunction "DB7_21") (pintype "passive+no_connect"))
    )
    (net (code "104") (name "unconnected-(LCD1-DB8-Pad20)") (class "Default")
      (node (ref "LCD1") (pin "20") (pinfunction "DB8_20") (pintype "passive+no_connect"))
    )
    (net (code "105") (name "unconnected-(LCD1-DB9-Pad19)") (class "Default")
      (node (ref "LCD1") (pin "19") (pinfunction "DB9_19") (pintype "passive+no_connect"))
    )
    (net (code "106") (name "unconnected-(LCD1-DB10-Pad18)") (class "Default")
      (node (ref "LCD1") (pin "18") (pinfunction "DB10_18") (pintype "passive+no_connect"))
    )
    (net (code "107") (name "unconnected-(LCD1-DB11-Pad17)") (class "Default")
      (node (ref "LCD1") (pin "17") (pinfunction "DB11_17") (pintype "passive+no_connect"))
    )
    (net (code "108") (name "unconnected-(LCD1-DB12-Pad16)") (class "Default")
      (node (ref "LCD1") (pin "16") (pinfunction "DB12_16") (pintype "passive+no_connect"))
    )
    (net (code "109") (name "unconnected-(LCD1-DB13-Pad15)") (class "Default")
      (node (ref "LCD1") (pin "15") (pinfunction "DB13_15") (pintype "passive+no_connect"))
    )
    (net (code "110") (name "unconnected-(LCD1-DB14-Pad14)") (class "Default")
      (node (ref "LCD1") (pin "14") (pinfunction "DB14_14") (pintype "passive+no_connect"))
    )
    (net (code "111") (name "unconnected-(LCD1-DB15-Pad13)") (class "Default")
      (node (ref "LCD1") (pin "13") (pinfunction "DB15_13") (pintype "passive+no_connect"))
    )
    (net (code "112") (name "unconnected-(LCD1-DB16-Pad12)") (class "Default")
      (node (ref "LCD1") (pin "12") (pinfunction "DB16_12") (pintype "passive+no_connect"))
    )
    (net (code "113") (name "unconnected-(LCD1-DB17-Pad11)") (class "Default")
      (node (ref "LCD1") (pin "11") (pinfunction "DB17_11") (pintype "passive+no_connect"))
    )
    (net (code "114") (name "unconnected-(LCD1-DOTCLK-Pad9)") (class "Default")
      (node (ref "LCD1") (pin "9") (pinfunction "DOTCLK_9") (pintype "passive+no_connect"))
    )
    (net (code "115") (name "unconnected-(LCD1-ENABLE-Pad10)") (class "Default")
      (node (ref "LCD1") (pin "10") (pinfunction "ENABLE_10") (pintype "passive+no_connect"))
    )
    (net (code "116") (name "unconnected-(LCD1-FMARK-Pad35)") (class "Default")
      (node (ref "LCD1") (pin "35") (pinfunction "FMARK_35") (pintype "passive+no_connect"))
    )
    (net (code "117") (name "unconnected-(LCD1-GND-Pad37)") (class "Default")
      (node (ref "LCD1") (pin "37") (pinfunction "GND_37") (pintype "passive+no_connect"))
    )
    (net (code "118") (name "unconnected-(LCD1-HSYNC-Pad7)") (class "Default")
      (node (ref "LCD1") (pin "7") (pinfunction "HSYNC_7") (pintype "passive+no_connect"))
    )
    (net (code "119") (name "unconnected-(LCD1-IM0-Pad2)") (class "Default")
      (node (ref "LCD1") (pin "2") (pinfunction "IM0_2") (pintype "passive+no_connect"))
    )
    (net (code "120") (name "unconnected-(LCD1-IM1-Pad3)") (class "Default")
      (node (ref "LCD1") (pin "3") (pinfunction "IM1_3") (pintype "passive+no_connect"))
    )
    (net (code "121") (name "unconnected-(LCD1-IM2-Pad4)") (class "Default")
      (node (ref "LCD1") (pin "4") (pinfunction "IM2_4") (pintype "passive+no_connect"))
    )
    (net (code "122") (name "unconnected-(LCD1-IM3-Pad5)") (class "Default")
      (node (ref "LCD1") (pin "5") (pinfunction "IM3_5") (pintype "passive+no_connect"))
    )
    (net (code "123") (name "unconnected-(LCD1-LED_A-Pad38)") (class "Default")
      (node (ref "LCD1") (pin "38") (pinfunction "LED_A_38") (pintype "passive+no_connect"))
    )
    (net (code "124") (name "unconnected-(LCD1-LED_K1-Pad39)") (class "Default")
      (node (ref "LCD1") (pin "39") (pinfunction "LED_K1_39") (pintype "passive+no_connect"))
    )
    (net (code "125") (name "unconnected-(LCD1-LED_K2-Pad40)") (class "Default")
      (node (ref "LCD1") (pin "40") (pinfunction "LED_K2_40") (pintype "passive+no_connect"))
    )
    (net (code "126") (name "unconnected-(LCD1-LED_K3-Pad41)") (class "Default")
      (node (ref "LCD1") (pin "41") (pinfunction "LED_K3_41") (pintype "passive+no_connect"))
    )
    (net (code "127") (name "unconnected-(LCD1-LED_K4-Pad1)") (class "Default")
      (node (ref "LCD1") (pin "1") (pinfunction "LED_K4_1") (pintype "passive+no_connect"))
    )
    (net (code "128") (name "unconnected-(LCD1-RD-Pad31)") (class "Default")
      (node (ref "LCD1") (pin "31") (pinfunction "RD_31") (pintype "passive+no_connect"))
    )
    (net (code "129") (name "unconnected-(LCD1-RESET-Pad6)") (class "Default")
      (node (ref "LCD1") (pin "6") (pinfunction "RESET_6") (pintype "passive+no_connect"))
    )
    (net (code "130") (name "unconnected-(LCD1-RS{slash}SCL-Pad32)") (class "Default")
      (node (ref "LCD1") (pin "32") (pinfunction "RS/SCL_32") (pintype "passive+no_connect"))
    )
    (net (code "131") (name "unconnected-(LCD1-SDI-Pad30)") (class "Default")
      (node (ref "LCD1") (pin "30") (pinfunction "SDI_30") (pintype "passive+no_connect"))
    )
    (net (code "132") (name "unconnected-(LCD1-SDO-Pad29)") (class "Default")
      (node (ref "LCD1") (pin "29") (pinfunction "SDO_29") (pintype "passive+no_connect"))
    )
    (net (code "133") (name "unconnected-(LCD1-VCC-Pad36)") (class "Default")
      (node (ref "LCD1") (pin "36") (pinfunction "VCC_36") (pintype "passive+no_connect"))
    )
    (net (code "134") (name "unconnected-(LCD1-VSYNC-Pad8)") (class "Default")
      (node (ref "LCD1") (pin "8") (pinfunction "VSYNC_8") (pintype "passive+no_connect"))
    )
    (net (code "135") (name "unconnected-(LCD1-WR-Pad33)") (class "Default")
      (node (ref "LCD1") (pin "33") (pinfunction "WR_33") (pintype "passive+no_connect"))
    )
    (net (code "136") (name "unconnected-(LCD1-XL<NC>-Pad45)") (class "Default")
      (node (ref "LCD1") (pin "45") (pinfunction "XL<NC>_45") (pintype "passive+no_connect"))
    )
    (net (code "137") (name "unconnected-(LCD1-XR<NC>-Pad43)") (class "Default")
      (node (ref "LCD1") (pin "43") (pinfunction "XR<NC>_43") (pintype "passive+no_connect"))
    )
    (net (code "138") (name "unconnected-(LCD1-YD<NC>-Pad42)") (class "Default")
      (node (ref "LCD1") (pin "42") (pinfunction "YD<NC>_42") (pintype "passive+no_connect"))
    )
    (net (code "139") (name "unconnected-(LCD1-YU<NC>-Pad44)") (class "Default")
      (node (ref "LCD1") (pin "44") (pinfunction "YU<NC>_44") (pintype "passive+no_connect"))
    )
  )
)
